# mapleCUx_large_083.net
KiCad netlist of a schematic drawn in EAGLE
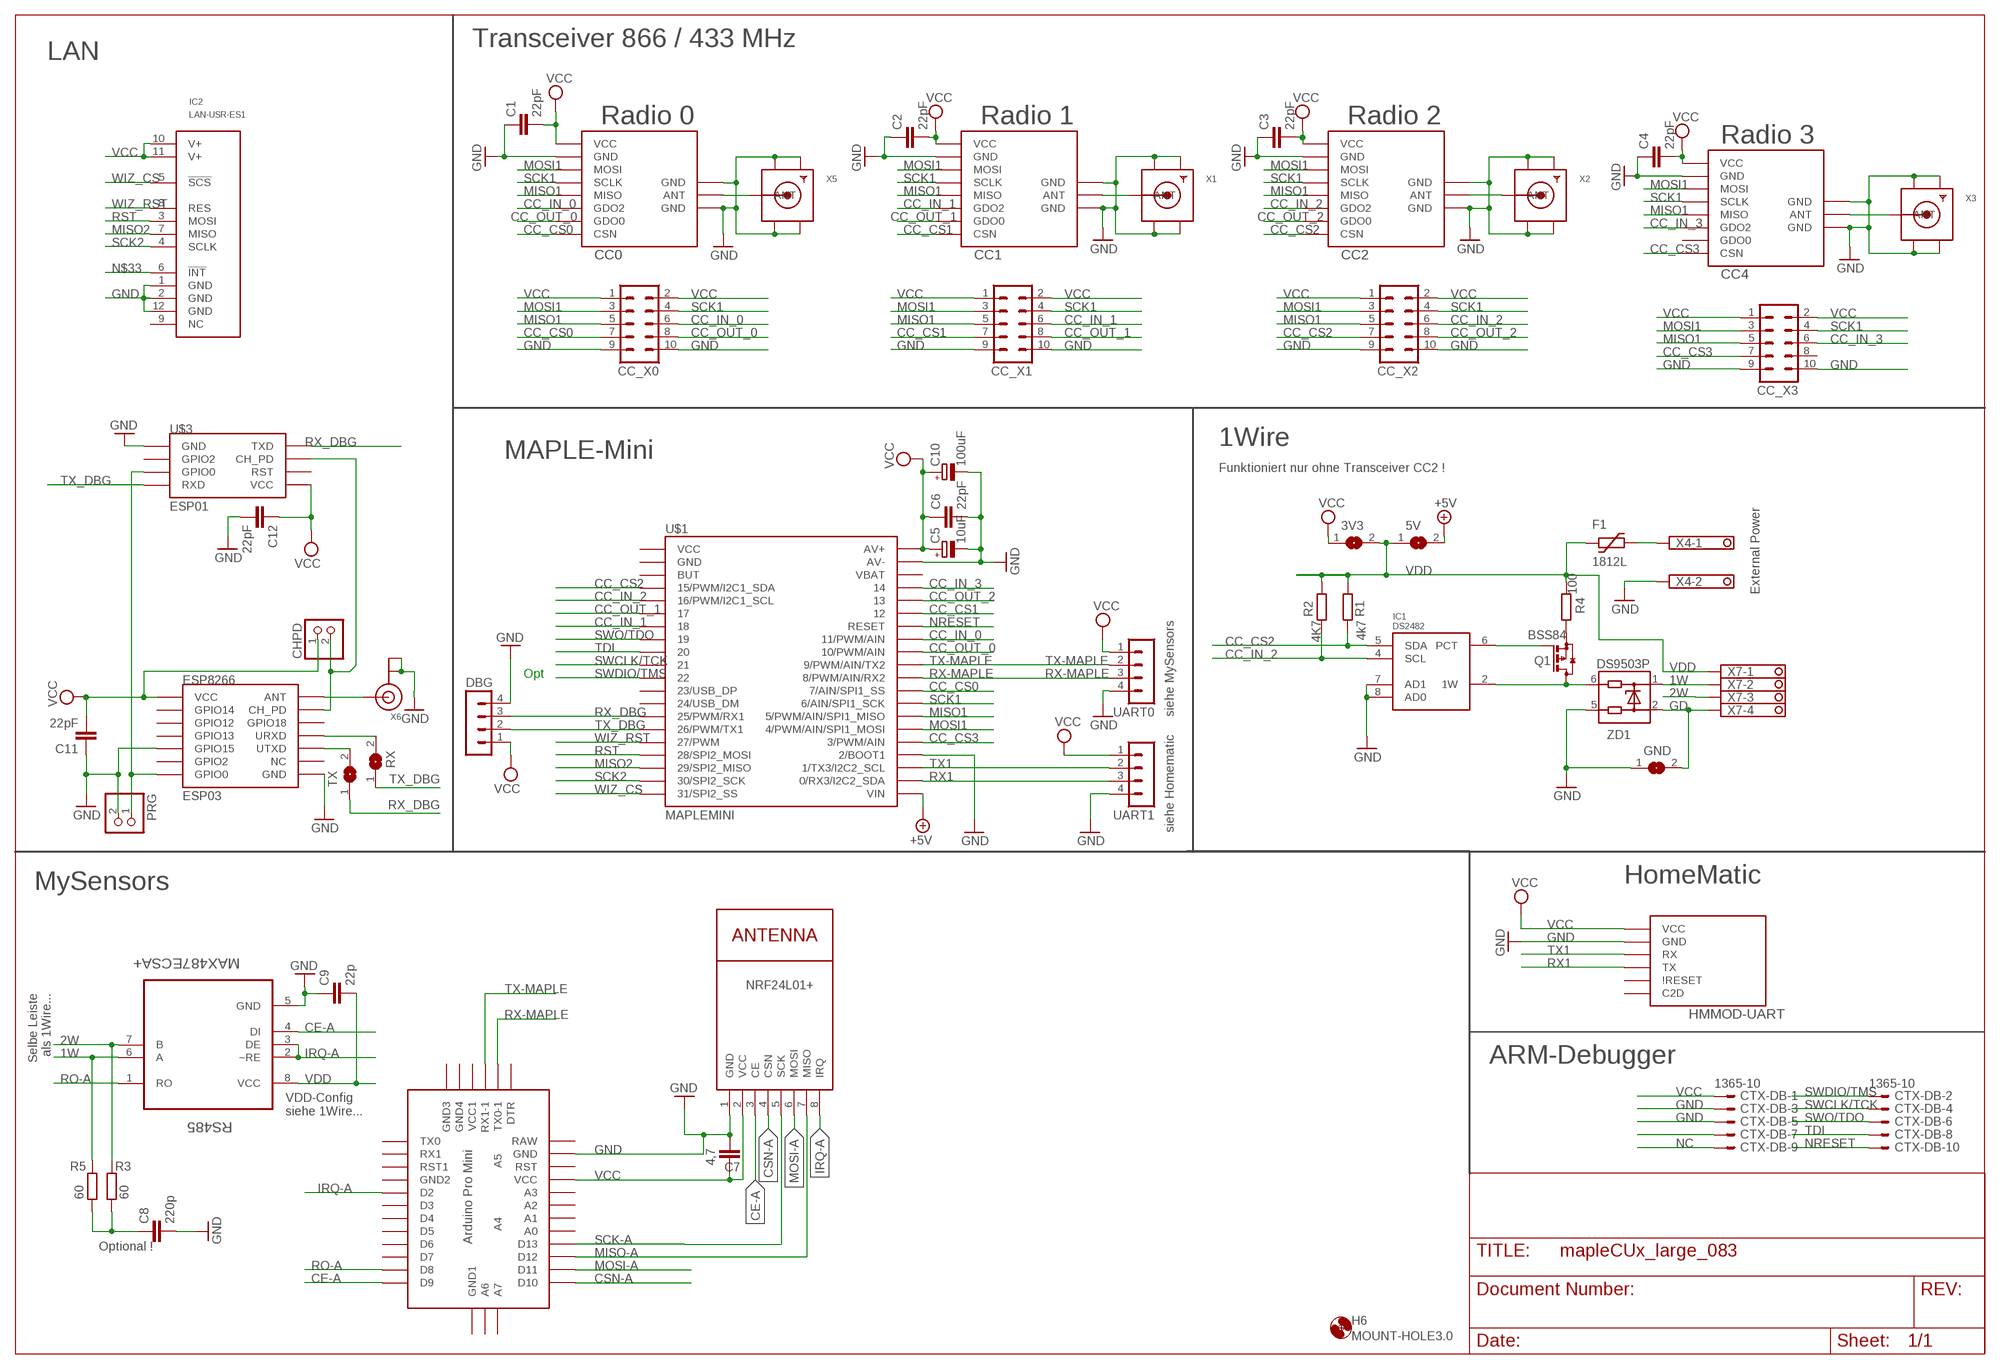
[diagram p0: schematic, sheet 1]

(export (version "E")
  (design (tool "Eeschema 10.0.6"))
  (components
    (comp (ref "3V3") (value "SJ") (footprint "eagle-import:SJ") (libsource (lib "eagle-import") (part "SJ")))
    (comp (ref "5V") (value "SJ") (footprint "eagle-import:SJ") (libsource (lib "eagle-import") (part "SJ")))
    (comp (ref "C1")
      (value "22pF")
      (footprint "eagle-import:C0805")
      (libsource (lib "eagle-import") (part "C-EUC0805"))
    )
    (comp (ref "C2")
      (value "22pF")
      (footprint "eagle-import:C0805")
      (libsource (lib "eagle-import") (part "C-EUC0805"))
    )
    (comp (ref "C3")
      (value "22pF")
      (footprint "eagle-import:C0805")
      (libsource (lib "eagle-import") (part "C-EUC0805"))
    )
    (comp (ref "C4")
      (value "22pF")
      (footprint "eagle-import:C0805")
      (libsource (lib "eagle-import") (part "C-EUC0805"))
    )
    (comp (ref "C5")
      (value "10uF")
      (footprint "eagle-import:R_2012-12W")
      (libsource (lib "eagle-import") (part "CPOL-EUR/2012-12W"))
    )
    (comp (ref "C6")
      (value "22pF")
      (footprint "eagle-import:C0805")
      (libsource (lib "eagle-import") (part "C-EUC0805"))
    )
    (comp (ref "C7")
      (value "4,7")
      (footprint "eagle-import:C1210")
      (libsource (lib "eagle-import") (part "C-EUC1210"))
    )
    (comp (ref "C8")
      (value "220p")
      (footprint "eagle-import:C0805")
      (libsource (lib "eagle-import") (part "C-EUC0805"))
    )
    (comp (ref "C9")
      (value "22p")
      (footprint "eagle-import:C0805")
      (libsource (lib "eagle-import") (part "C-EUC0805"))
    )
    (comp (ref "C10")
      (value "100uF")
      (footprint "eagle-import:E5-8,5")
      (libsource (lib "eagle-import") (part "CPOL-EUE5-8.5"))
    )
    (comp (ref "C11")
      (value "22pF")
      (footprint "eagle-import:C0805")
      (libsource (lib "eagle-import") (part "C-EUC0805"))
    )
    (comp (ref "C12")
      (value "22pF")
      (footprint "eagle-import:C0805")
      (libsource (lib "eagle-import") (part "C-EUC0805"))
    )
    (comp (ref "CC0")
      (value "CC1101")
      (footprint "eagle-import:CC1101_MODULE1_SMD")
      (libsource (lib "eagle-import") (part "CC1101_MODULE1SMD"))
    )
    (comp (ref "CC1")
      (value "CC1101_MODULE1SMD")
      (footprint "eagle-import:CC1101_MODULE1_SMD")
      (libsource (lib "eagle-import") (part "CC1101_MODULE1SMD"))
    )
    (comp (ref "CC2")
      (value "CC1101_MODULE1SMD")
      (footprint "eagle-import:CC1101_MODULE1_SMD")
      (libsource (lib "eagle-import") (part "CC1101_MODULE1SMD"))
    )
    (comp (ref "CC4")
      (value "CC1101_MODULE1SMD")
      (footprint "eagle-import:CC1101_MODULE1_SMD")
      (libsource (lib "eagle-import") (part "CC1101_MODULE1SMD"))
    )
    (comp (ref "CC_X0")
      (value "MA05-2")
      (footprint "eagle-import:MA05-2")
      (libsource (lib "eagle-import") (part "MA05-2"))
    )
    (comp (ref "CC_X1")
      (value "MA05-2")
      (footprint "eagle-import:MA05-2")
      (libsource (lib "eagle-import") (part "MA05-2"))
    )
    (comp (ref "CC_X2")
      (value "MA05-2")
      (footprint "eagle-import:MA05-2")
      (libsource (lib "eagle-import") (part "MA05-2"))
    )
    (comp (ref "CC_X3")
      (value "MA05-2")
      (footprint "eagle-import:MA05-2")
      (libsource (lib "eagle-import") (part "MA05-2"))
    )
    (comp (ref "CHPD")
      (value "PINHD-1X2")
      (footprint "eagle-import:1X02")
      (libsource (lib "eagle-import") (part "PINHD-1X2"))
    )
    (comp (ref "CTX-DB")
      (value "1365-10")
      (footprint "eagle-import:1365-10")
      (libsource (lib "eagle-import") (part "1365-10"))
    )
    (comp (ref "DBG")
      (value "MA04-1")
      (footprint "eagle-import:MA04-1")
      (libsource (lib "eagle-import") (part "MA04-1"))
    )
    (comp (ref "ESP8266")
      (value "ESP03")
      (footprint "eagle-import:ESP03")
      (libsource (lib "eagle-import") (part "ESP03"))
    )
    (comp (ref "F1")
      (value "1812L")
      (footprint "eagle-import:1812L")
      (libsource (lib "eagle-import") (part "1812L"))
    )
    (comp (ref "GND") (value "SJ") (footprint "eagle-import:SJ") (libsource (lib "eagle-import") (part "SJ")))
    (comp (ref "H6")
      (value "MOUNT-HOLE3.0")
      (footprint "eagle-import:3,0")
      (libsource (lib "eagle-import") (part "MOUNT-HOLE3.0"))
    )
    (comp (ref "HMMOD-UART")
      (value "HM-MOD-UARTDIL")
      (footprint "eagle-import:HM-MOD-UART-DIL")
      (libsource (lib "eagle-import") (part "HM-MOD-UARTDIL"))
    )
    (comp (ref "IC1")
      (value "DS2482")
      (footprint "eagle-import:SO08")
      (libsource (lib "eagle-import") (part "DS2482-100S"))
    )
    (comp (ref "IC2")
      (value "LAN-USR-ES1")
      (footprint "eagle-import:USR-ES1")
      (libsource (lib "eagle-import") (part "LAN-USR-ES1"))
    )
    (comp (ref "NRF24L01+")
      (value "NRF24L01+")
      (footprint "eagle-import:WIRELESS-NRF24L01")
      (libsource (lib "eagle-import") (part "WIRELESS-NRF24L01"))
    )
    (comp (ref "PRG")
      (value "PINHD-1X2")
      (footprint "eagle-import:1X02")
      (libsource (lib "eagle-import") (part "PINHD-1X2"))
    )
    (comp (ref "Q1")
      (value "BSS84")
      (footprint "eagle-import:SOT23")
      (libsource (lib "eagle-import") (part "BSS84"))
    )
    (comp (ref "R1")
      (value "4k7")
      (footprint "eagle-import:R0805")
      (libsource (lib "eagle-import") (part "R-EU_R0805"))
    )
    (comp (ref "R2")
      (value "4K7")
      (footprint "eagle-import:R0805")
      (libsource (lib "eagle-import") (part "R-EU_R0805"))
    )
    (comp (ref "R3")
      (value "60")
      (footprint "eagle-import:R0805")
      (libsource (lib "eagle-import") (part "R-EU_R0805"))
    )
    (comp (ref "R4")
      (value "100")
      (footprint "eagle-import:R0805")
      (libsource (lib "eagle-import") (part "R-EU_R0805"))
    )
    (comp (ref "R5")
      (value "60")
      (footprint "eagle-import:R0805")
      (libsource (lib "eagle-import") (part "R-EU_R0805"))
    )
    (comp (ref "RS485")
      (value "MAX487ECSA+")
      (footprint "eagle-import:SOIC127P600X175-8N")
      (libsource (lib "eagle-import") (part "MAX487ECSA+"))
    )
    (comp (ref "RX") (value "SJ") (footprint "eagle-import:SJ") (libsource (lib "eagle-import") (part "SJ")))
    (comp (ref "TX") (value "SJ") (footprint "eagle-import:SJ") (libsource (lib "eagle-import") (part "SJ")))
    (comp (ref "U$1")
      (value "MAPLEMINI")
      (footprint "eagle-import:20-DIP")
      (libsource (lib "eagle-import") (part "MAPLEMINI"))
    )
    (comp (ref "U$2")
      (value "ABK-PRO-MINI")
      (footprint "eagle-import:ABK-PRO-MINI")
      (libsource (lib "eagle-import") (part "ABK-PRO-MINI"))
    )
    (comp (ref "U$3")
      (value "ESP01")
      (footprint "eagle-import:ESP01")
      (libsource (lib "eagle-import") (part "ESP01"))
    )
    (comp (ref "UART0")
      (value "MA04-1")
      (footprint "eagle-import:MA04-1")
      (libsource (lib "eagle-import") (part "MA04-1"))
    )
    (comp (ref "UART1")
      (value "MA04-1")
      (footprint "eagle-import:MA04-1")
      (libsource (lib "eagle-import") (part "MA04-1"))
    )
    (comp (ref "X1")
      (value "SMACONNECTOR_EDGE_UFL")
      (footprint "eagle-import:SMA_EDGELAUNCH_UFL")
      (libsource (lib "eagle-import") (part "SMACONNECTOR_EDGE_UFL"))
    )
    (comp (ref "X2")
      (value "SMACONNECTOR_EDGE_UFL")
      (footprint "eagle-import:SMA_EDGELAUNCH_UFL")
      (libsource (lib "eagle-import") (part "SMACONNECTOR_EDGE_UFL"))
    )
    (comp (ref "X3")
      (value "SMACONNECTOR_EDGE_UFL")
      (footprint "eagle-import:SMA_EDGELAUNCH_UFL")
      (libsource (lib "eagle-import") (part "SMACONNECTOR_EDGE_UFL"))
    )
    (comp (ref "X4")
      (value "1751248")
      (footprint "eagle-import:1751248")
      (libsource (lib "eagle-import") (part "1751248"))
    )
    (comp (ref "X5")
      (value "SMACONNECTOR_EDGE_UFL")
      (footprint "eagle-import:SMA_EDGELAUNCH_UFL")
      (libsource (lib "eagle-import") (part "SMACONNECTOR_EDGE_UFL"))
    )
    (comp (ref "X6")
      (value "ANTENNA_U.FL")
      (footprint "eagle-import:U.FL")
      (libsource (lib "eagle-import") (part "ANTENNA_U.FL"))
    )
    (comp (ref "X7")
      (value "1751264")
      (footprint "eagle-import:1751264")
      (libsource (lib "eagle-import") (part "1751264"))
    )
    (comp (ref "ZD1")
      (value "DS9503P")
      (footprint "eagle-import:TSOC6")
      (libsource (lib "eagle-import") (part "DS9503P"))
    )
  )
  (nets
    (net (code "1") (name "+5V") (class "Default")
      (node (ref "5V") (pin "2") (pinfunction "2_2") (pintype "passive"))
      (node (ref "U$1") (pin "21") (pinfunction "VIN_21") (pintype "bidirectional"))
    )
    (net (code "2") (name "/1W") (class "Default")
      (node (ref "R5") (pin "2") (pinfunction "2_2") (pintype "passive"))
      (node (ref "RS485") (pin "6") (pinfunction "A_6") (pintype "bidirectional"))
      (node (ref "X7") (pin "2") (pinfunction "K_2") (pintype "passive"))
      (node (ref "ZD1") (pin "1") (pinfunction "P$1_1") (pintype "passive"))
    )
    (net (code "3") (name "/2W") (class "Default")
      (node (ref "R3") (pin "2") (pinfunction "2_2") (pintype "passive"))
      (node (ref "RS485") (pin "7") (pinfunction "B_7") (pintype "bidirectional"))
      (node (ref "X7") (pin "3") (pinfunction "K_3") (pintype "passive"))
    )
    (net (code "4") (name "/CC_CS0") (class "Default")
      (node (ref "CC0") (pin "CSN") (pinfunction "CSN_CSN") (pintype "bidirectional"))
      (node (ref "CC_X0") (pin "7") (pinfunction "7_7") (pintype "passive"))
      (node (ref "U$1") (pin "29") (pinfunction "7/AIN/SPI1_SS_29") (pintype "bidirectional"))
    )
    (net (code "5") (name "/CC_CS1") (class "Default")
      (node (ref "CC1") (pin "CSN") (pinfunction "CSN_CSN") (pintype "bidirectional"))
      (node (ref "CC_X1") (pin "7") (pinfunction "7_7") (pintype "passive"))
      (node (ref "U$1") (pin "35") (pinfunction "12_35") (pintype "bidirectional"))
    )
    (net (code "6") (name "/CC_CS2") (class "Default")
      (node (ref "CC2") (pin "CSN") (pinfunction "CSN_CSN") (pintype "bidirectional"))
      (node (ref "CC_X2") (pin "7") (pinfunction "7_7") (pintype "passive"))
      (node (ref "IC1") (pin "5") (pinfunction "SDA_5") (pintype "bidirectional"))
      (node (ref "R1") (pin "2") (pinfunction "2_2") (pintype "passive"))
      (node (ref "U$1") (pin "4") (pinfunction "15/PWM/I2C1_SDA_4") (pintype "bidirectional"))
    )
    (net (code "7") (name "/CC_CS3") (class "Default")
      (node (ref "CC4") (pin "CSN") (pinfunction "CSN_CSN") (pintype "bidirectional"))
      (node (ref "CC_X3") (pin "7") (pinfunction "7_7") (pintype "passive"))
      (node (ref "U$1") (pin "25") (pinfunction "3/PWM/AIN_25") (pintype "bidirectional"))
    )
    (net (code "8") (name "/CC_IN_0") (class "Default")
      (node (ref "CC0") (pin "GDO2") (pinfunction "GDO2_GDO2") (pintype "bidirectional"))
      (node (ref "CC_X0") (pin "6") (pinfunction "6_6") (pintype "passive"))
      (node (ref "U$1") (pin "33") (pinfunction "11/PWM/AIN_33") (pintype "bidirectional"))
    )
    (net (code "9") (name "/CC_IN_1") (class "Default")
      (node (ref "CC1") (pin "GDO2") (pinfunction "GDO2_GDO2") (pintype "bidirectional"))
      (node (ref "CC_X1") (pin "6") (pinfunction "6_6") (pintype "passive"))
      (node (ref "U$1") (pin "7") (pinfunction "18_7") (pintype "bidirectional"))
    )
    (net (code "10") (name "/CC_IN_2") (class "Default")
      (node (ref "CC2") (pin "GDO2") (pinfunction "GDO2_GDO2") (pintype "bidirectional"))
      (node (ref "CC_X2") (pin "6") (pinfunction "6_6") (pintype "passive"))
      (node (ref "IC1") (pin "4") (pinfunction "SCL_4") (pintype "input"))
      (node (ref "R2") (pin "2") (pinfunction "2_2") (pintype "passive"))
      (node (ref "U$1") (pin "5") (pinfunction "16/PWM/I2C1_SCL_5") (pintype "bidirectional"))
    )
    (net (code "11") (name "/CC_IN_3") (class "Default")
      (node (ref "CC4") (pin "GDO2") (pinfunction "GDO2_GDO2") (pintype "bidirectional"))
      (node (ref "CC_X3") (pin "6") (pinfunction "6_6") (pintype "passive"))
      (node (ref "U$1") (pin "37") (pinfunction "14_37") (pintype "bidirectional"))
    )
    (net (code "12") (name "/CC_OUT_0") (class "Default")
      (node (ref "CC0") (pin "GDO0") (pinfunction "GDO0_GDO0") (pintype "bidirectional"))
      (node (ref "CC_X0") (pin "8") (pinfunction "8_8") (pintype "passive"))
      (node (ref "U$1") (pin "32") (pinfunction "10/PWM/AIN_32") (pintype "bidirectional"))
    )
    (net (code "13") (name "/CC_OUT_1") (class "Default")
      (node (ref "CC1") (pin "GDO0") (pinfunction "GDO0_GDO0") (pintype "bidirectional"))
      (node (ref "CC_X1") (pin "8") (pinfunction "8_8") (pintype "passive"))
      (node (ref "U$1") (pin "6") (pinfunction "17_6") (pintype "bidirectional"))
    )
    (net (code "14") (name "/CC_OUT_2") (class "Default")
      (node (ref "CC2") (pin "GDO0") (pinfunction "GDO0_GDO0") (pintype "bidirectional"))
      (node (ref "CC_X2") (pin "8") (pinfunction "8_8") (pintype "passive"))
      (node (ref "U$1") (pin "36") (pinfunction "13_36") (pintype "bidirectional"))
    )
    (net (code "15") (name "/GD") (class "Default")
      (node (ref "GND") (pin "2") (pinfunction "2_2") (pintype "passive"))
      (node (ref "X7") (pin "4") (pinfunction "K_4") (pintype "passive"))
      (node (ref "ZD1") (pin "2") (pinfunction "P$2_2") (pintype "passive"))
    )
    (net (code "16") (name "/MISO-A") (class "Default")
      (node (ref "NRF24L01+") (pin "7") (pinfunction "MISO_7") (pintype "bidirectional"))
      (node (ref "U$2") (pin "D12") (pinfunction "D12_D12") (pintype "bidirectional"))
    )
    (net (code "17") (name "/MISO1") (class "Default")
      (node (ref "CC0") (pin "MISO") (pinfunction "MISO_MISO") (pintype "bidirectional"))
      (node (ref "CC1") (pin "MISO") (pinfunction "MISO_MISO") (pintype "bidirectional"))
      (node (ref "CC2") (pin "MISO") (pinfunction "MISO_MISO") (pintype "bidirectional"))
      (node (ref "CC4") (pin "MISO") (pinfunction "MISO_MISO") (pintype "bidirectional"))
      (node (ref "CC_X0") (pin "5") (pinfunction "5_5") (pintype "passive"))
      (node (ref "CC_X1") (pin "5") (pinfunction "5_5") (pintype "passive"))
      (node (ref "CC_X2") (pin "5") (pinfunction "5_5") (pintype "passive"))
      (node (ref "CC_X3") (pin "5") (pinfunction "5_5") (pintype "passive"))
      (node (ref "U$1") (pin "27") (pinfunction "5/PWM/AIN/SPI1_MISO_27") (pintype "bidirectional"))
    )
    (net (code "18") (name "/MISO2") (class "Default")
      (node (ref "IC2") (pin "7") (pinfunction "MISO_7") (pintype "bidirectional"))
      (node (ref "U$1") (pin "18") (pinfunction "29/SPI2_MISO_18") (pintype "bidirectional"))
    )
    (net (code "19") (name "/MOSI1") (class "Default")
      (node (ref "CC0") (pin "MOSI") (pinfunction "MOSI_MOSI") (pintype "bidirectional"))
      (node (ref "CC1") (pin "MOSI") (pinfunction "MOSI_MOSI") (pintype "bidirectional"))
      (node (ref "CC2") (pin "MOSI") (pinfunction "MOSI_MOSI") (pintype "bidirectional"))
      (node (ref "CC4") (pin "MOSI") (pinfunction "MOSI_MOSI") (pintype "bidirectional"))
      (node (ref "CC_X0") (pin "3") (pinfunction "3_3") (pintype "passive"))
      (node (ref "CC_X1") (pin "3") (pinfunction "3_3") (pintype "passive"))
      (node (ref "CC_X2") (pin "3") (pinfunction "3_3") (pintype "passive"))
      (node (ref "CC_X3") (pin "3") (pinfunction "3_3") (pintype "passive"))
      (node (ref "U$1") (pin "26") (pinfunction "4/PWM/AIN/SPI1_MOSI_26") (pintype "bidirectional"))
    )
    (net (code "20") (name "/N$33") (class "Default")
      (node (ref "IC2") (pin "6") (pinfunction "~{INT}_6") (pintype "output"))
    )
    (net (code "21") (name "/NC") (class "Default")
      (node (ref "CTX-DB") (pin "9") (pinfunction "S_9") (pintype "passive"))
    )
    (net (code "22") (name "/NRESET") (class "Default")
      (node (ref "CTX-DB") (pin "10") (pinfunction "S_10") (pintype "passive"))
      (node (ref "U$1") (pin "34") (pinfunction "RESET_34") (pintype "bidirectional"))
    )
    (net (code "23") (name "/RO-A") (class "Default")
      (node (ref "RS485") (pin "1") (pinfunction "RO_1") (pintype "output"))
      (node (ref "U$2") (pin "D8") (pinfunction "D8_D8") (pintype "bidirectional"))
    )
    (net (code "24") (name "/RST") (class "Default")
      (node (ref "IC2") (pin "3") (pinfunction "MOSI_3") (pintype "bidirectional"))
      (node (ref "U$1") (pin "17") (pinfunction "28/SPI2_MOSI_17") (pintype "bidirectional"))
    )
    (net (code "25") (name "/RX-MAPLE") (class "Default")
      (node (ref "U$1") (pin "30") (pinfunction "8/PWM/AIN/RX2_30") (pintype "bidirectional"))
      (node (ref "U$2") (pin "TX0-1") (pinfunction "TX0-1_TX0-1") (pintype "bidirectional"))
      (node (ref "UART0") (pin "3") (pinfunction "3_3") (pintype "passive"))
    )
    (net (code "26") (name "/RX1") (class "Default")
      (node (ref "HMMOD-UART") (pin "5") (pinfunction "TX_5") (pintype "bidirectional"))
      (node (ref "U$1") (pin "22") (pinfunction "0/RX3/I2C2_SDA_22") (pintype "bidirectional"))
      (node (ref "UART1") (pin "3") (pinfunction "3_3") (pintype "passive"))
    )
    (net (code "27") (name "/RX_DBG") (class "Default")
      (node (ref "DBG") (pin "3") (pinfunction "3_3") (pintype "passive"))
      (node (ref "TX") (pin "1") (pinfunction "1_1") (pintype "passive"))
      (node (ref "U$1") (pin "14") (pinfunction "25/PWM/RX1_14") (pintype "bidirectional"))
      (node (ref "U$3") (pin "TX") (pinfunction "TXD_TX") (pintype "bidirectional"))
    )
    (net (code "28") (name "/SCK-A") (class "Default")
      (node (ref "NRF24L01+") (pin "5") (pinfunction "SCK_5") (pintype "bidirectional"))
      (node (ref "U$2") (pin "D13") (pinfunction "D13_D13") (pintype "bidirectional"))
    )
    (net (code "29") (name "/SCK1") (class "Default")
      (node (ref "CC0") (pin "SCLK") (pinfunction "SCLK_SCLK") (pintype "bidirectional"))
      (node (ref "CC1") (pin "SCLK") (pinfunction "SCLK_SCLK") (pintype "bidirectional"))
      (node (ref "CC2") (pin "SCLK") (pinfunction "SCLK_SCLK") (pintype "bidirectional"))
      (node (ref "CC4") (pin "SCLK") (pinfunction "SCLK_SCLK") (pintype "bidirectional"))
      (node (ref "CC_X0") (pin "4") (pinfunction "4_4") (pintype "passive"))
      (node (ref "CC_X1") (pin "4") (pinfunction "4_4") (pintype "passive"))
      (node (ref "CC_X2") (pin "4") (pinfunction "4_4") (pintype "passive"))
      (node (ref "CC_X3") (pin "4") (pinfunction "4_4") (pintype "passive"))
      (node (ref "U$1") (pin "28") (pinfunction "6/AIN/SPI1_SCK_28") (pintype "bidirectional"))
    )
    (net (code "30") (name "/SCK2") (class "Default")
      (node (ref "IC2") (pin "4") (pinfunction "SCLK_4") (pintype "input"))
      (node (ref "U$1") (pin "19") (pinfunction "30/SPI2_SCK_19") (pintype "bidirectional"))
    )
    (net (code "31") (name "/SWCLK{slash}TCK") (class "Default")
      (node (ref "CTX-DB") (pin "4") (pinfunction "S_4") (pintype "passive"))
      (node (ref "U$1") (pin "10") (pinfunction "21_10") (pintype "bidirectional"))
    )
    (net (code "32") (name "/SWDIO{slash}TMS") (class "Default")
      (node (ref "CTX-DB") (pin "2") (pinfunction "S_2") (pintype "passive"))
      (node (ref "U$1") (pin "11") (pinfunction "22_11") (pintype "bidirectional"))
    )
    (net (code "33") (name "/SWO{slash}TDO") (class "Default")
      (node (ref "CTX-DB") (pin "6") (pinfunction "S_6") (pintype "passive"))
      (node (ref "U$1") (pin "8") (pinfunction "19_8") (pintype "bidirectional"))
    )
    (net (code "34") (name "/TDI") (class "Default")
      (node (ref "CTX-DB") (pin "8") (pinfunction "S_8") (pintype "passive"))
      (node (ref "U$1") (pin "9") (pinfunction "20_9") (pintype "bidirectional"))
    )
    (net (code "35") (name "/TX-MAPLE") (class "Default")
      (node (ref "U$1") (pin "31") (pinfunction "9/PWM/AIN/TX2_31") (pintype "bidirectional"))
      (node (ref "U$2") (pin "RX1-1") (pinfunction "RX1-1_RX1-1") (pintype "bidirectional"))
      (node (ref "UART0") (pin "2") (pinfunction "2_2") (pintype "passive"))
    )
    (net (code "36") (name "/TX1") (class "Default")
      (node (ref "HMMOD-UART") (pin "6") (pinfunction "RX_6") (pintype "bidirectional"))
      (node (ref "U$1") (pin "23") (pinfunction "1/TX3/I2C2_SCL_23") (pintype "bidirectional"))
      (node (ref "UART1") (pin "2") (pinfunction "2_2") (pintype "passive"))
    )
    (net (code "37") (name "/TX_DBG") (class "Default")
      (node (ref "DBG") (pin "2") (pinfunction "2_2") (pintype "passive"))
      (node (ref "RX") (pin "1") (pinfunction "1_1") (pintype "passive"))
      (node (ref "U$1") (pin "15") (pinfunction "26/PWM/TX1_15") (pintype "bidirectional"))
      (node (ref "U$3") (pin "RX") (pinfunction "RXD_RX") (pintype "bidirectional"))
    )
    (net (code "38") (name "/VDD") (class "Default")
      (node (ref "3V3") (pin "2") (pinfunction "2_2") (pintype "passive"))
      (node (ref "5V") (pin "1") (pinfunction "1_1") (pintype "passive"))
      (node (ref "C9") (pin "2") (pinfunction "2_2") (pintype "passive"))
      (node (ref "F1") (pin "P$1") (pinfunction "1_P$1") (pintype "passive"))
      (node (ref "R1") (pin "1") (pinfunction "1_1") (pintype "passive"))
      (node (ref "R2") (pin "1") (pinfunction "1_1") (pintype "passive"))
      (node (ref "R4") (pin "2") (pinfunction "2_2") (pintype "passive"))
      (node (ref "RS485") (pin "8") (pinfunction "VCC_8") (pintype "power_in"))
      (node (ref "X7") (pin "1") (pinfunction "K_1") (pintype "passive"))
    )
    (net (code "39") (name "/WIZ_CS") (class "Default")
      (node (ref "IC2") (pin "5") (pinfunction "~{SCS}_5") (pintype "input"))
      (node (ref "U$1") (pin "20") (pinfunction "31/SPI2_SS_20") (pintype "bidirectional"))
    )
    (net (code "40") (name "/WIZ_RST") (class "Default")
      (node (ref "IC2") (pin "8") (pinfunction "RES_8") (pintype "input"))
      (node (ref "U$1") (pin "16") (pinfunction "27/PWM_16") (pintype "bidirectional"))
    )
    (net (code "41") (name "CE-A") (class "Default")
      (node (ref "NRF24L01+") (pin "3") (pinfunction "CE_3") (pintype "bidirectional"))
      (node (ref "RS485") (pin "4") (pinfunction "DI_4") (pintype "input"))
      (node (ref "U$2") (pin "D9") (pinfunction "D9_D9") (pintype "bidirectional"))
    )
    (net (code "42") (name "CSN-A") (class "Default")
      (node (ref "NRF24L01+") (pin "4") (pinfunction "CSN_4") (pintype "bidirectional"))
      (node (ref "U$2") (pin "D10") (pinfunction "D10_D10") (pintype "bidirectional"))
    )
    (net (code "43") (name "GND") (class "Default")
      (node (ref "C1") (pin "1") (pinfunction "1_1") (pintype "passive"))
      (node (ref "C10") (pin "-") (pinfunction "-_-") (pintype "passive"))
      (node (ref "C11") (pin "1") (pinfunction "1_1") (pintype "passive"))
      (node (ref "C12") (pin "2") (pinfunction "2_2") (pintype "passive"))
      (node (ref "C2") (pin "1") (pinfunction "1_1") (pintype "passive"))
      (node (ref "C3") (pin "1") (pinfunction "1_1") (pintype "passive"))
      (node (ref "C4") (pin "1") (pinfunction "1_1") (pintype "passive"))
      (node (ref "C5") (pin "-") (pinfunction "-_-") (pintype "passive"))
      (node (ref "C6") (pin "2") (pinfunction "2_2") (pintype "passive"))
      (node (ref "C7") (pin "1") (pinfunction "1_1") (pintype "passive"))
      (node (ref "C8") (pin "2") (pinfunction "2_2") (pintype "passive"))
      (node (ref "C9") (pin "1") (pinfunction "1_1") (pintype "passive"))
      (node (ref "CC0") (pin "GND@0") (pinfunction "GND_GND@0") (pintype "power_in"))
      (node (ref "CC0") (pin "GND@1") (pinfunction "GND_GND@1") (pintype "power_in"))
      (node (ref "CC0") (pin "GND@2") (pinfunction "GND_GND@2") (pintype "power_in"))
      (node (ref "CC1") (pin "GND@0") (pinfunction "GND_GND@0") (pintype "power_in"))
      (node (ref "CC1") (pin "GND@1") (pinfunction "GND_GND@1") (pintype "power_in"))
      (node (ref "CC1") (pin "GND@2") (pinfunction "GND_GND@2") (pintype "power_in"))
      (node (ref "CC2") (pin "GND@0") (pinfunction "GND_GND@0") (pintype "power_in"))
      (node (ref "CC2") (pin "GND@1") (pinfunction "GND_GND@1") (pintype "power_in"))
      (node (ref "CC2") (pin "GND@2") (pinfunction "GND_GND@2") (pintype "power_in"))
      (node (ref "CC4") (pin "GND@0") (pinfunction "GND_GND@0") (pintype "power_in"))
      (node (ref "CC4") (pin "GND@1") (pinfunction "GND_GND@1") (pintype "power_in"))
      (node (ref "CC4") (pin "GND@2") (pinfunction "GND_GND@2") (pintype "power_in"))
      (node (ref "CC_X0") (pin "10") (pinfunction "10_10") (pintype "passive"))
      (node (ref "CC_X0") (pin "9") (pinfunction "9_9") (pintype "passive"))
      (node (ref "CC_X1") (pin "10") (pinfunction "10_10") (pintype "passive"))
      (node (ref "CC_X1") (pin "9") (pinfunction "9_9") (pintype "passive"))
      (node (ref "CC_X2") (pin "10") (pinfunction "10_10") (pintype "passive"))
      (node (ref "CC_X2") (pin "9") (pinfunction "9_9") (pintype "passive"))
      (node (ref "CC_X3") (pin "10") (pinfunction "10_10") (pintype "passive"))
      (node (ref "CC_X3") (pin "9") (pinfunction "9_9") (pintype "passive"))
      (node (ref "CTX-DB") (pin "3") (pinfunction "S_3") (pintype "passive"))
      (node (ref "CTX-DB") (pin "5") (pinfunction "S_5") (pintype "passive"))
      (node (ref "DBG") (pin "4") (pinfunction "4_4") (pintype "passive"))
      (node (ref "ESP8266") (pin "GND") (pinfunction "GND_GND") (pintype "bidirectional"))
      (node (ref "ESP8266") (pin "GPIO15") (pinfunction "GPIO15_GPIO15") (pintype "bidirectional"))
      (node (ref "GND") (pin "1") (pinfunction "1_1") (pintype "passive"))
      (node (ref "HMMOD-UART") (pin "2") (pinfunction "GND_2") (pintype "power_in"))
      (node (ref "IC1") (pin "7") (pinfunction "AD1_7") (pintype "input"))
      (node (ref "IC1") (pin "8") (pinfunction "AD0_8") (pintype "input"))
      (node (ref "IC2") (pin "1") (pinfunction "GND_1") (pintype "power_in"))
      (node (ref "IC2") (pin "12") (pinfunction "GND_12") (pintype "power_in"))
      (node (ref "IC2") (pin "2") (pinfunction "GND_2") (pintype "power_in"))
      (node (ref "NRF24L01+") (pin "1") (pinfunction "GND_1") (pintype "power_in"))
      (node (ref "PRG") (pin "2") (pinfunction "2_2") (pintype "passive"))
      (node (ref "RS485") (pin "5") (pinfunction "GND_5") (pintype "passive"))
      (node (ref "U$1") (pin "24") (pinfunction "2/BOOT1_24") (pintype "bidirectional"))
      (node (ref "U$1") (pin "39") (pinfunction "AV-_39") (pintype "bidirectional"))
      (node (ref "U$2") (pin "GND") (pinfunction "GND_GND") (pintype "bidirectional"))
      (node (ref "U$3") (pin "GND") (pinfunction "GND_GND") (pintype "bidirectional"))
      (node (ref "UART0") (pin "4") (pinfunction "4_4") (pintype "passive"))
      (node (ref "UART1") (pin "4") (pinfunction "4_4") (pintype "passive"))
      (node (ref "X1") (pin "GND@1") (pinfunction "GND1_GND@1") (pintype "power_in"))
      (node (ref "X1") (pin "GND@2") (pinfunction "GND2_GND@2") (pintype "power_in"))
      (node (ref "X1") (pin "GND@3") (pinfunction "GND3_GND@3") (pintype "power_in"))
      (node (ref "X1") (pin "GND@4") (pinfunction "GND4_GND@4") (pintype "power_in"))
      (node (ref "X2") (pin "GND@1") (pinfunction "GND1_GND@1") (pintype "power_in"))
      (node (ref "X2") (pin "GND@2") (pinfunction "GND2_GND@2") (pintype "power_in"))
      (node (ref "X2") (pin "GND@3") (pinfunction "GND3_GND@3") (pintype "power_in"))
      (node (ref "X2") (pin "GND@4") (pinfunction "GND4_GND@4") (pintype "power_in"))
      (node (ref "X3") (pin "GND@1") (pinfunction "GND1_GND@1") (pintype "power_in"))
      (node (ref "X3") (pin "GND@2") (pinfunction "GND2_GND@2") (pintype "power_in"))
      (node (ref "X3") (pin "GND@3") (pinfunction "GND3_GND@3") (pintype "power_in"))
      (node (ref "X3") (pin "GND@4") (pinfunction "GND4_GND@4") (pintype "power_in"))
      (node (ref "X4") (pin "2") (pinfunction "K_2") (pintype "passive"))
      (node (ref "X5") (pin "GND@1") (pinfunction "GND1_GND@1") (pintype "power_in"))
      (node (ref "X5") (pin "GND@2") (pinfunction "GND2_GND@2") (pintype "power_in"))
      (node (ref "X5") (pin "GND@3") (pinfunction "GND3_GND@3") (pintype "power_in"))
      (node (ref "X5") (pin "GND@4") (pinfunction "GND4_GND@4") (pintype "power_in"))
      (node (ref "X6") (pin "1") (pinfunction "GND_1") (pintype "passive"))
      (node (ref "X6") (pin "2") (pinfunction "GND_2") (pintype "passive"))
      (node (ref "ZD1") (pin "5") (pinfunction "P$3_5") (pintype "passive"))
    )
    (net (code "44") (name "IRQ-A") (class "Default")
      (node (ref "NRF24L01+") (pin "8") (pinfunction "IRQ_8") (pintype "bidirectional"))
      (node (ref "RS485") (pin "2") (pinfunction "~{RE}_2") (pintype "input"))
      (node (ref "RS485") (pin "3") (pinfunction "DE_3") (pintype "input"))
      (node (ref "U$2") (pin "D2") (pinfunction "D2_D2") (pintype "bidirectional"))
    )
    (net (code "45") (name "MOSI-A") (class "Default")
      (node (ref "NRF24L01+") (pin "6") (pinfunction "MOSI_6") (pintype "bidirectional"))
      (node (ref "U$2") (pin "D11") (pinfunction "D11_D11") (pintype "bidirectional"))
    )
    (net (code "46") (name "Net-(C8-Pad1)") (class "Default")
      (node (ref "C8") (pin "1") (pinfunction "1_1") (pintype "passive"))
      (node (ref "R3") (pin "1") (pinfunction "1_1") (pintype "passive"))
      (node (ref "R5") (pin "1") (pinfunction "1_1") (pintype "passive"))
    )
    (net (code "47") (name "Net-(CHPD-Pad2)") (class "Default")
      (node (ref "CHPD") (pin "2") (pinfunction "2_2") (pintype "passive"))
      (node (ref "ESP8266") (pin "CH_PD") (pinfunction "CH_PD_CH_PD") (pintype "bidirectional"))
      (node (ref "U$3") (pin "CH_PD") (pinfunction "CH_PD_CH_PD") (pintype "bidirectional"))
    )
    (net (code "48") (name "Net-(ESP8266-PadGPIO0)") (class "Default")
      (node (ref "ESP8266") (pin "GPIO0") (pinfunction "GPIO0_GPIO0") (pintype "bidirectional"))
      (node (ref "PRG") (pin "1") (pinfunction "1_1") (pintype "passive"))
      (node (ref "U$3") (pin "GPIO0") (pinfunction "GPIO0_GPIO0") (pintype "bidirectional"))
    )
    (net (code "49") (name "Net-(ESP8266-PadURXD)") (class "Default")
      (node (ref "ESP8266") (pin "URXD") (pinfunction "URXD_URXD") (pintype "bidirectional"))
      (node (ref "RX") (pin "2") (pinfunction "2_2") (pintype "passive"))
    )
    (net (code "50") (name "Net-(ESP8266-PadUTXD)") (class "Default")
      (node (ref "ESP8266") (pin "UTXD") (pinfunction "UTXD_UTXD") (pintype "bidirectional"))
      (node (ref "TX") (pin "2") (pinfunction "2_2") (pintype "passive"))
    )
    (net (code "51") (name "Net-(F1-2)") (class "Default")
      (node (ref "F1") (pin "P$2") (pinfunction "2_P$2") (pintype "passive"))
      (node (ref "X4") (pin "1") (pinfunction "K_1") (pintype "passive"))
    )
    (net (code "52") (name "Net-(IC1A-1W)") (class "Default")
      (node (ref "IC1") (pin "2") (pinfunction "1W_2") (pintype "open_collector"))
      (node (ref "Q1") (pin "3") (pinfunction "D_3") (pintype "passive"))
      (node (ref "ZD1") (pin "6") (pinfunction "P$4_6") (pintype "passive"))
    )
    (net (code "53") (name "Net-(IC1A-PCT)") (class "Default")
      (node (ref "IC1") (pin "6") (pinfunction "PCT_6") (pintype "output"))
      (node (ref "Q1") (pin "1") (pinfunction "G_1") (pintype "passive"))
    )
    (net (code "54") (name "Net-(Q1-S)") (class "Default")
      (node (ref "Q1") (pin "2") (pinfunction "S_2") (pintype "passive"))
      (node (ref "R4") (pin "1") (pinfunction "1_1") (pintype "passive"))
    )
    (net (code "55") (name "Net-(X1-ANT)") (class "Default")
      (node (ref "CC1") (pin "ANT") (pinfunction "ANT_ANT") (pintype "output"))
      (node (ref "X1") (pin "P") (pinfunction "ANT_P") (pintype "bidirectional"))
    )
    (net (code "56") (name "Net-(X2-ANT)") (class "Default")
      (node (ref "CC2") (pin "ANT") (pinfunction "ANT_ANT") (pintype "output"))
      (node (ref "X2") (pin "P") (pinfunction "ANT_P") (pintype "bidirectional"))
    )
    (net (code "57") (name "Net-(X3-ANT)") (class "Default")
      (node (ref "CC4") (pin "ANT") (pinfunction "ANT_ANT") (pintype "output"))
      (node (ref "X3") (pin "P") (pinfunction "ANT_P") (pintype "bidirectional"))
    )
    (net (code "58") (name "Net-(X5-ANT)") (class "Default")
      (node (ref "CC0") (pin "ANT") (pinfunction "ANT_ANT") (pintype "output"))
      (node (ref "X5") (pin "P") (pinfunction "ANT_P") (pintype "bidirectional"))
    )
    (net (code "59") (name "Net-(X6-SIGNAL)") (class "Default")
      (node (ref "ESP8266") (pin "ANT") (pinfunction "ANT_ANT") (pintype "bidirectional"))
      (node (ref "X6") (pin "3") (pinfunction "SIGNAL_3") (pintype "passive"))
    )
    (net (code "60") (name "VCC") (class "Default")
      (node (ref "3V3") (pin "1") (pinfunction "1_1") (pintype "passive"))
      (node (ref "C1") (pin "2") (pinfunction "2_2") (pintype "passive"))
      (node (ref "C10") (pin "+") (pinfunction "+_+") (pintype "passive"))
      (node (ref "C11") (pin "2") (pinfunction "2_2") (pintype "passive"))
      (node (ref "C12") (pin "1") (pinfunction "1_1") (pintype "passive"))
      (node (ref "C2") (pin "2") (pinfunction "2_2") (pintype "passive"))
      (node (ref "C3") (pin "2") (pinfunction "2_2") (pintype "passive"))
      (node (ref "C4") (pin "2") (pinfunction "2_2") (pintype "passive"))
      (node (ref "C5") (pin "+") (pinfunction "+_+") (pintype "passive"))
      (node (ref "C6") (pin "1") (pinfunction "1_1") (pintype "passive"))
      (node (ref "C7") (pin "2") (pinfunction "2_2") (pintype "passive"))
      (node (ref "CC0") (pin "VCC") (pinfunction "VCC_VCC") (pintype "power_in"))
      (node (ref "CC1") (pin "VCC") (pinfunction "VCC_VCC") (pintype "power_in"))
      (node (ref "CC2") (pin "VCC") (pinfunction "VCC_VCC") (pintype "power_in"))
      (node (ref "CC4") (pin "VCC") (pinfunction "VCC_VCC") (pintype "power_in"))
      (node (ref "CC_X0") (pin "1") (pinfunction "1_1") (pintype "passive"))
      (node (ref "CC_X0") (pin "2") (pinfunction "2_2") (pintype "passive"))
      (node (ref "CC_X1") (pin "1") (pinfunction "1_1") (pintype "passive"))
      (node (ref "CC_X1") (pin "2") (pinfunction "2_2") (pintype "passive"))
      (node (ref "CC_X2") (pin "1") (pinfunction "1_1") (pintype "passive"))
      (node (ref "CC_X2") (pin "2") (pinfunction "2_2") (pintype "passive"))
      (node (ref "CC_X3") (pin "1") (pinfunction "1_1") (pintype "passive"))
      (node (ref "CC_X3") (pin "2") (pinfunction "2_2") (pintype "passive"))
      (node (ref "CHPD") (pin "1") (pinfunction "1_1") (pintype "passive"))
      (node (ref "CTX-DB") (pin "1") (pinfunction "S_1") (pintype "passive"))
      (node (ref "DBG") (pin "1") (pinfunction "1_1") (pintype "passive"))
      (node (ref "ESP8266") (pin "VCC") (pinfunction "VCC_VCC") (pintype "bidirectional"))
      (node (ref "HMMOD-UART") (pin "1") (pinfunction "VCC_1") (pintype "power_in"))
      (node (ref "IC2") (pin "10") (pinfunction "V+_10") (pintype "power_in"))
      (node (ref "IC2") (pin "11") (pinfunction "V+_11") (pintype "power_in"))
      (node (ref "NRF24L01+") (pin "2") (pinfunction "VCC_2") (pintype "power_in"))
      (node (ref "U$1") (pin "40") (pinfunction "AV+_40") (pintype "bidirectional"))
      (node (ref "U$2") (pin "VCC") (pinfunction "VCC_VCC") (pintype "bidirectional"))
      (node (ref "U$3") (pin "VCC") (pinfunction "VCC_VCC") (pintype "bidirectional"))
      (node (ref "UART0") (pin "1") (pinfunction "1_1") (pintype "passive"))
      (node (ref "UART1") (pin "1") (pinfunction "1_1") (pintype "passive"))
    )
    (net (code "61") (name "unconnected-(CC4-PadGDO0)") (class "Default")
      (node (ref "CC4") (pin "GDO0") (pinfunction "GDO0_GDO0") (pintype "bidirectional"))
    )
    (net (code "62") (name "unconnected-(CC_X3-Pad8)") (class "Default")
      (node (ref "CC_X3") (pin "8") (pinfunction "8_8") (pintype "passive"))
    )
    (net (code "63") (name "unconnected-(CTX-DBH-S-Pad7)") (class "Default")
      (node (ref "CTX-DB") (pin "7") (pinfunction "S_7") (pintype "passive"))
    )
    (net (code "64") (name "unconnected-(ESP8266-PadGPIO2)") (class "Default")
      (node (ref "ESP8266") (pin "GPIO2") (pinfunction "GPIO2_GPIO2") (pintype "bidirectional"))
    )
    (net (code "65") (name "unconnected-(ESP8266-PadGPIO12)") (class "Default")
      (node (ref "ESP8266") (pin "GPIO12") (pinfunction "GPIO12_GPIO12") (pintype "bidirectional"))
    )
    (net (code "66") (name "unconnected-(ESP8266-PadGPIO13)") (class "Default")
      (node (ref "ESP8266") (pin "GPIO13") (pinfunction "GPIO13_GPIO13") (pintype "bidirectional"))
    )
    (net (code "67") (name "unconnected-(ESP8266-PadGPIO14)") (class "Default")
      (node (ref "ESP8266") (pin "GPIO14") (pinfunction "GPIO14_GPIO14") (pintype "bidirectional"))
    )
    (net (code "68") (name "unconnected-(ESP8266-PadGPIO18)") (class "Default")
      (node (ref "ESP8266") (pin "GPIO18") (pinfunction "GPIO18_GPIO18") (pintype "bidirectional"))
    )
    (net (code "69") (name "unconnected-(ESP8266-PadNC)") (class "Default")
      (node (ref "ESP8266") (pin "NC") (pinfunction "NC_NC") (pintype "bidirectional"))
    )
    (net (code "70") (name "unconnected-(HMMOD-UART-C2D-Pad3)") (class "Default")
      (node (ref "HMMOD-UART") (pin "3") (pinfunction "C2D_3") (pintype "bidirectional"))
    )
    (net (code "71") (name "unconnected-(HMMOD-UART-\\~{RESET}-Pad4)") (class "Default")
      (node (ref "HMMOD-UART") (pin "4") (pinfunction "\\~{RESET}_4") (pintype "bidirectional"))
    )
    (net (code "72") (name "unconnected-(IC2-NC-Pad9)") (class "Default")
      (node (ref "IC2") (pin "9") (pinfunction "NC_9") (pintype "no_connect"))
    )
    (net (code "73") (name "unconnected-(U$1-23{slash}USB_DP-Pad12)") (class "Default")
      (node (ref "U$1") (pin "12") (pinfunction "23/USB_DP_12") (pintype "bidirectional"))
    )
    (net (code "74") (name "unconnected-(U$1-24{slash}USB_DM-Pad13)") (class "Default")
      (node (ref "U$1") (pin "13") (pinfunction "24/USB_DM_13") (pintype "bidirectional"))
    )
    (net (code "75") (name "unconnected-(U$1-BUT-Pad3)") (class "Default")
      (node (ref "U$1") (pin "3") (pinfunction "BUT_3") (pintype "bidirectional"))
    )
    (net (code "76") (name "unconnected-(U$1-GND-Pad2)") (class "Default")
      (node (ref "U$1") (pin "2") (pinfunction "GND_2") (pintype "bidirectional"))
    )
    (net (code "77") (name "unconnected-(U$1-VBAT-Pad38)") (class "Default")
      (node (ref "U$1") (pin "38") (pinfunction "VBAT_38") (pintype "bidirectional"))
    )
    (net (code "78") (name "unconnected-(U$1-VCC-Pad1)") (class "Default")
      (node (ref "U$1") (pin "1") (pinfunction "VCC_1") (pintype "bidirectional"))
    )
    (net (code "79") (name "unconnected-(U$2-GND1-PadGND4)") (class "Default")
      (node (ref "U$2") (pin "GND4") (pinfunction "GND1_GND4") (pintype "bidirectional"))
    )
    (net (code "80") (name "unconnected-(U$2-GND2-PadGND1)") (class "Default")
      (node (ref "U$2") (pin "GND1") (pinfunction "GND2_GND1") (pintype "bidirectional"))
    )
    (net (code "81") (name "unconnected-(U$2-GND3-PadGND2)") (class "Default")
      (node (ref "U$2") (pin "GND2") (pinfunction "GND3_GND2") (pintype "bidirectional"))
    )
    (net (code "82") (name "unconnected-(U$2-GND4-PadGND3)") (class "Default")
      (node (ref "U$2") (pin "GND3") (pinfunction "GND4_GND3") (pintype "bidirectional"))
    )
    (net (code "83") (name "unconnected-(U$2-PadA0)") (class "Default")
      (node (ref "U$2") (pin "A0") (pinfunction "A0_A0") (pintype "bidirectional"))
    )
    (net (code "84") (name "unconnected-(U$2-PadA1)") (class "Default")
      (node (ref "U$2") (pin "A1") (pinfunction "A1_A1") (pintype "bidirectional"))
    )
    (net (code "85") (name "unconnected-(U$2-PadA2)") (class "Default")
      (node (ref "U$2") (pin "A2") (pinfunction "A2_A2") (pintype "bidirectional"))
    )
    (net (code "86") (name "unconnected-(U$2-PadA3)") (class "Default")
      (node (ref "U$2") (pin "A3") (pinfunction "A3_A3") (pintype "bidirectional"))
    )
    (net (code "87") (name "unconnected-(U$2-PadA4)") (class "Default")
      (node (ref "U$2") (pin "A4") (pinfunction "A4_A4") (pintype "bidirectional"))
    )
    (net (code "88") (name "unconnected-(U$2-PadA5)") (class "Default")
      (node (ref "U$2") (pin "A5") (pinfunction "A5_A5") (pintype "bidirectional"))
    )
    (net (code "89") (name "unconnected-(U$2-PadA6)") (class "Default")
      (node (ref "U$2") (pin "A6") (pinfunction "A6_A6") (pintype "bidirectional"))
    )
    (net (code "90") (name "unconnected-(U$2-PadA7)") (class "Default")
      (node (ref "U$2") (pin "A7") (pinfunction "A7_A7") (pintype "bidirectional"))
    )
    (net (code "91") (name "unconnected-(U$2-PadD3)") (class "Default")
      (node (ref "U$2") (pin "D3") (pinfunction "D3_D3") (pintype "bidirectional"))
    )
    (net (code "92") (name "unconnected-(U$2-PadD4)") (class "Default")
      (node (ref "U$2") (pin "D4") (pinfunction "D4_D4") (pintype "bidirectional"))
    )
    (net (code "93") (name "unconnected-(U$2-PadD5)") (class "Default")
      (node (ref "U$2") (pin "D5") (pinfunction "D5_D5") (pintype "bidirectional"))
    )
    (net (code "94") (name "unconnected-(U$2-PadD6)") (class "Default")
      (node (ref "U$2") (pin "D6") (pinfunction "D6_D6") (pintype "bidirectional"))
    )
    (net (code "95") (name "unconnected-(U$2-PadD7)") (class "Default")
      (node (ref "U$2") (pin "D7") (pinfunction "D7_D7") (pintype "bidirectional"))
    )
    (net (code "96") (name "unconnected-(U$2-PadDTR)") (class "Default")
      (node (ref "U$2") (pin "DTR") (pinfunction "DTR_DTR") (pintype "bidirectional"))
    )
    (net (code "97") (name "unconnected-(U$2-PadRAW)") (class "Default")
      (node (ref "U$2") (pin "RAW") (pinfunction "RAW_RAW") (pintype "bidirectional"))
    )
    (net (code "98") (name "unconnected-(U$2-PadRST)") (class "Default")
      (node (ref "U$2") (pin "RST") (pinfunction "RST_RST") (pintype "bidirectional"))
    )
    (net (code "99") (name "unconnected-(U$2-PadRST1)") (class "Default")
      (node (ref "U$2") (pin "RST1") (pinfunction "RST1_RST1") (pintype "bidirectional"))
    )
    (net (code "100") (name "unconnected-(U$2-PadRX1)") (class "Default")
      (node (ref "U$2") (pin "RX1") (pinfunction "RX1_RX1") (pintype "bidirectional"))
    )
    (net (code "101") (name "unconnected-(U$2-PadTX0)") (class "Default")
      (node (ref "U$2") (pin "TX0") (pinfunction "TX0_TX0") (pintype "bidirectional"))
    )
    (net (code "102") (name "unconnected-(U$2-PadVCC1)") (class "Default")
      (node (ref "U$2") (pin "VCC1") (pinfunction "VCC1_VCC1") (pintype "bidirectional"))
    )
    (net (code "103") (name "unconnected-(U$3-PadGPIO2)") (class "Default")
      (node (ref "U$3") (pin "GPIO2") (pinfunction "GPIO2_GPIO2") (pintype "bidirectional"))
    )
    (net (code "104") (name "unconnected-(U$3-PadRST)") (class "Default")
      (node (ref "U$3") (pin "RST") (pinfunction "RST_RST") (pintype "bidirectional"))
    )
  )
)
